# 12_USB3_0_power.net
KiCad netlist of a schematic drawn in Altium Designer
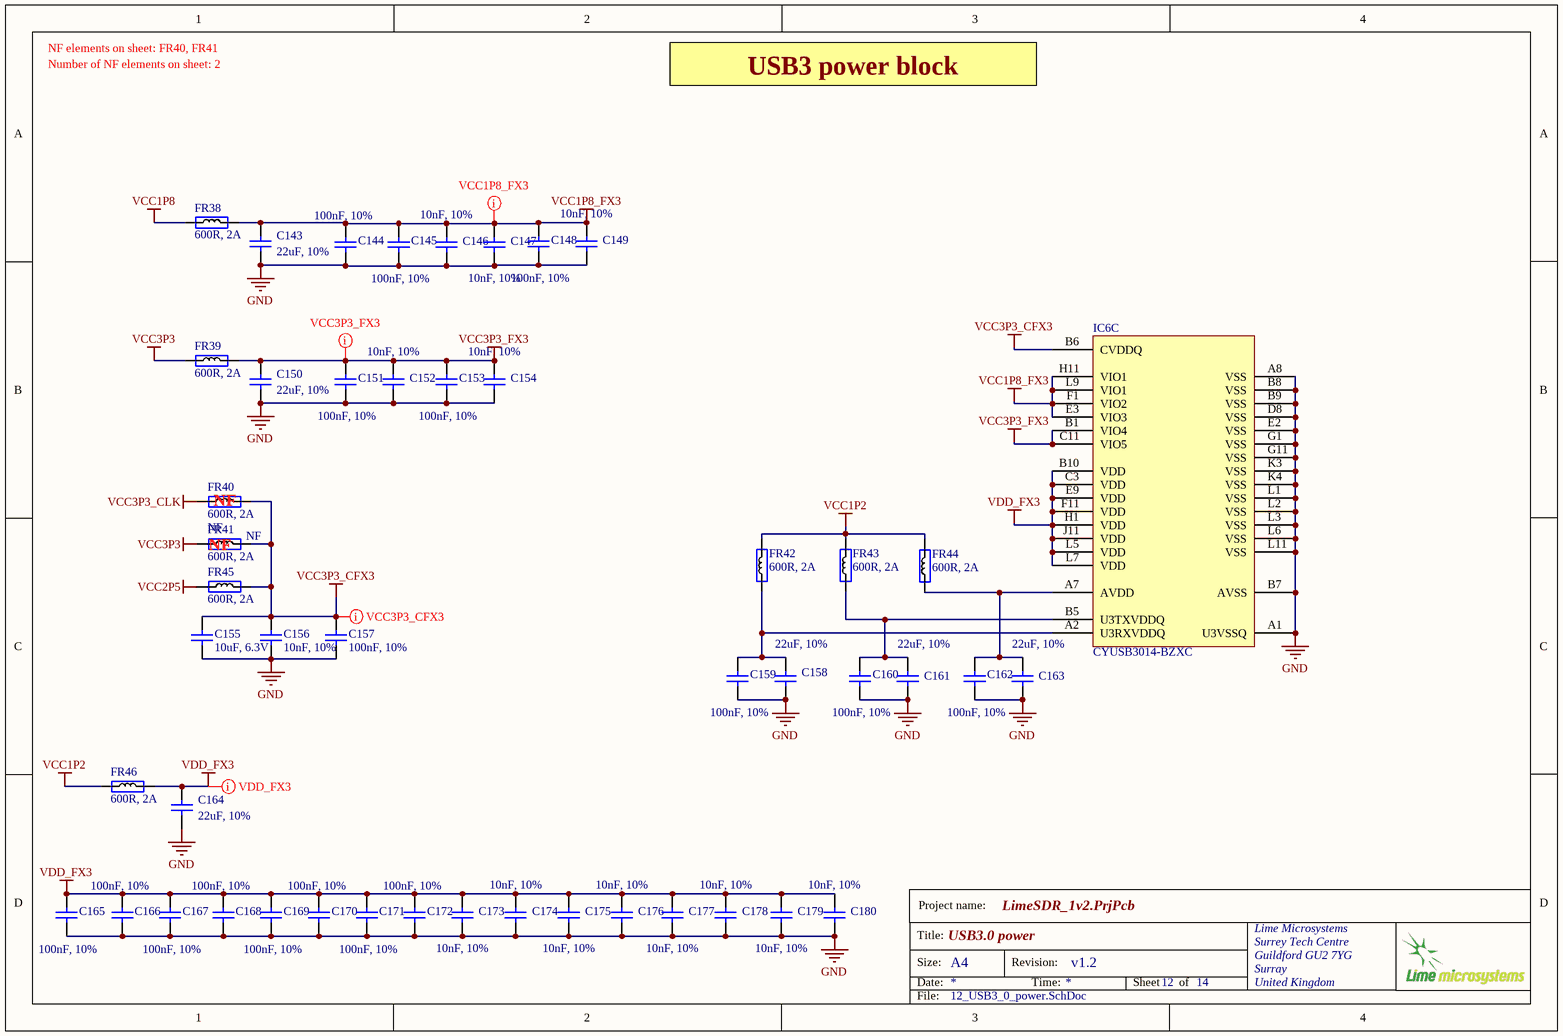
[diagram p0: 12_USB3_0_power.SchDoc]

(export (version "E")
  (design (tool "Eeschema 10.0.6"))
  (components
    (comp (ref "C143")
      (value "22uF, 10%")
      (footprint "CAP0603")
      (fields (field (name "TOLERANCE") "20 %"))
      (libsource (lib "LimeFPGAboard_schLib") (part "Cap_0603"))
    )
    (comp (ref "C144")
      (value "100nF, 10%")
      (footprint "CAP0402")
      (fields
        (field (name "TOLERANCE") "10 %")
        (field (name "MANUFACTURER") "Murata Electronics")
        (field (name "MANUFACTURER PART NUMBER") "GRM155R71C104KA88D")
      )
      (libsource (lib "LimeFPGAboard_schLib") (part "Cap_0603"))
    )
    (comp (ref "C145")
      (value "100nF, 10%")
      (footprint "CAP0402")
      (fields
        (field (name "TOLERANCE") "10 %")
        (field (name "MANUFACTURER") "Murata Electronics")
        (field (name "MANUFACTURER PART NUMBER") "GRM155R71C104KA88D")
      )
      (libsource (lib "LimeFPGAboard_schLib") (part "Cap_0603"))
    )
    (comp (ref "C146")
      (value "10nF, 10%")
      (footprint "CAP0402")
      (fields (field (name "TOLERANCE") "±10%") (field (name "MANUFACTURER") "Yageo"))
      (libsource (lib "LimeFPGAboard_schLib") (part "Cap_0603"))
    )
    (comp (ref "C147")
      (value "10nF, 10%")
      (footprint "CAP0402")
      (fields (field (name "TOLERANCE") "±10%") (field (name "MANUFACTURER") "Yageo"))
      (libsource (lib "LimeFPGAboard_schLib") (part "Cap_0603"))
    )
    (comp (ref "C148")
      (value "100nF, 10%")
      (footprint "CAP0402")
      (fields
        (field (name "TOLERANCE") "10 %")
        (field (name "MANUFACTURER") "Murata Electronics")
        (field (name "MANUFACTURER PART NUMBER") "GRM155R71C104KA88D")
      )
      (libsource (lib "LimeFPGAboard_schLib") (part "Cap_0603"))
    )
    (comp (ref "C149")
      (value "10nF, 10%")
      (footprint "CAP0402")
      (fields (field (name "TOLERANCE") "±10%") (field (name "MANUFACTURER") "Yageo"))
      (libsource (lib "LimeFPGAboard_schLib") (part "Cap_0603"))
    )
    (comp (ref "C150")
      (value "22uF, 10%")
      (footprint "CAP0603")
      (fields (field (name "TOLERANCE") "20 %"))
      (libsource (lib "LimeFPGAboard_schLib") (part "Cap_0603"))
    )
    (comp (ref "C151")
      (value "100nF, 10%")
      (footprint "CAP0402")
      (fields
        (field (name "TOLERANCE") "10 %")
        (field (name "MANUFACTURER") "Murata Electronics")
        (field (name "MANUFACTURER PART NUMBER") "GRM155R71C104KA88D")
      )
      (libsource (lib "LimeFPGAboard_schLib") (part "Cap_0603"))
    )
    (comp (ref "C152")
      (value "10nF, 10%")
      (footprint "CAP0402")
      (fields (field (name "TOLERANCE") "±10%") (field (name "MANUFACTURER") "Yageo"))
      (libsource (lib "LimeFPGAboard_schLib") (part "Cap_0603"))
    )
    (comp (ref "C153")
      (value "100nF, 10%")
      (footprint "CAP0402")
      (fields
        (field (name "TOLERANCE") "10 %")
        (field (name "MANUFACTURER") "Murata Electronics")
        (field (name "MANUFACTURER PART NUMBER") "GRM155R71C104KA88D")
      )
      (libsource (lib "LimeFPGAboard_schLib") (part "Cap_0603"))
    )
    (comp (ref "C154")
      (value "10nF, 10%")
      (footprint "CAP0402")
      (fields (field (name "TOLERANCE") "±10%") (field (name "MANUFACTURER") "Yageo"))
      (libsource (lib "LimeFPGAboard_schLib") (part "Cap_0603"))
    )
    (comp (ref "C155")
      (value "10uF, 6.3V")
      (footprint "CAP0603")
      (fields (field (name "TOLERANCE") "±20%") (field (name "MANUFACTURER") "Yageo"))
      (libsource (lib "LimeFPGAboard_schLib") (part "Cap_0603"))
    )
    (comp (ref "C156")
      (value "10nF, 10%")
      (footprint "CAP0402")
      (fields (field (name "TOLERANCE") "±10%") (field (name "MANUFACTURER") "Yageo"))
      (libsource (lib "LimeFPGAboard_schLib") (part "Cap_0603"))
    )
    (comp (ref "C157")
      (value "100nF, 10%")
      (footprint "CAP0402")
      (fields
        (field (name "TOLERANCE") "10 %")
        (field (name "MANUFACTURER") "Murata Electronics")
        (field (name "MANUFACTURER PART NUMBER") "GRM155R71C104KA88D")
      )
      (libsource (lib "LimeFPGAboard_schLib") (part "Cap_0603"))
    )
    (comp (ref "C158")
      (value "22uF, 10%")
      (footprint "CAP0603")
      (fields (field (name "TOLERANCE") "20 %"))
      (libsource (lib "LimeFPGAboard_schLib") (part "Cap_0603"))
    )
    (comp (ref "C159")
      (value "100nF, 10%")
      (footprint "CAP0402")
      (fields
        (field (name "TOLERANCE") "10 %")
        (field (name "MANUFACTURER") "Murata Electronics")
        (field (name "MANUFACTURER PART NUMBER") "GRM155R71C104KA88D")
      )
      (libsource (lib "LimeFPGAboard_schLib") (part "Cap_0603"))
    )
    (comp (ref "C160")
      (value "100nF, 10%")
      (footprint "CAP0402")
      (fields
        (field (name "TOLERANCE") "10 %")
        (field (name "MANUFACTURER") "Murata Electronics")
        (field (name "MANUFACTURER PART NUMBER") "GRM155R71C104KA88D")
      )
      (libsource (lib "LimeFPGAboard_schLib") (part "Cap_0603"))
    )
    (comp (ref "C161")
      (value "22uF, 10%")
      (footprint "CAP0603")
      (fields (field (name "TOLERANCE") "20 %"))
      (libsource (lib "LimeFPGAboard_schLib") (part "Cap_0603"))
    )
    (comp (ref "C162")
      (value "100nF, 10%")
      (footprint "CAP0402")
      (fields
        (field (name "TOLERANCE") "10 %")
        (field (name "MANUFACTURER") "Murata Electronics")
        (field (name "MANUFACTURER PART NUMBER") "GRM155R71C104KA88D")
      )
      (libsource (lib "LimeFPGAboard_schLib") (part "Cap_0603"))
    )
    (comp (ref "C163")
      (value "22uF, 10%")
      (footprint "CAP0603")
      (fields (field (name "TOLERANCE") "20 %"))
      (libsource (lib "LimeFPGAboard_schLib") (part "Cap_0603"))
    )
    (comp (ref "C164")
      (value "22uF, 10%")
      (footprint "CAP0603")
      (fields (field (name "TOLERANCE") "20 %"))
      (libsource (lib "LimeFPGAboard_schLib") (part "Cap_0603"))
    )
    (comp (ref "C165")
      (value "100nF, 10%")
      (footprint "CAP0402")
      (fields
        (field (name "TOLERANCE") "10 %")
        (field (name "MANUFACTURER") "Murata Electronics")
        (field (name "MANUFACTURER PART NUMBER") "GRM155R71C104KA88D")
      )
      (libsource (lib "LimeFPGAboard_schLib") (part "Cap_0603"))
    )
    (comp (ref "C166")
      (value "100nF, 10%")
      (footprint "CAP0402")
      (fields
        (field (name "TOLERANCE") "10 %")
        (field (name "MANUFACTURER") "Murata Electronics")
        (field (name "MANUFACTURER PART NUMBER") "GRM155R71C104KA88D")
      )
      (libsource (lib "LimeFPGAboard_schLib") (part "Cap_0603"))
    )
    (comp (ref "C167")
      (value "100nF, 10%")
      (footprint "CAP0402")
      (fields
        (field (name "TOLERANCE") "10 %")
        (field (name "MANUFACTURER") "Murata Electronics")
        (field (name "MANUFACTURER PART NUMBER") "GRM155R71C104KA88D")
      )
      (libsource (lib "LimeFPGAboard_schLib") (part "Cap_0603"))
    )
    (comp (ref "C168")
      (value "100nF, 10%")
      (footprint "CAP0402")
      (fields
        (field (name "TOLERANCE") "10 %")
        (field (name "MANUFACTURER") "Murata Electronics")
        (field (name "MANUFACTURER PART NUMBER") "GRM155R71C104KA88D")
      )
      (libsource (lib "LimeFPGAboard_schLib") (part "Cap_0603"))
    )
    (comp (ref "C169")
      (value "100nF, 10%")
      (footprint "CAP0402")
      (fields
        (field (name "TOLERANCE") "10 %")
        (field (name "MANUFACTURER") "Murata Electronics")
        (field (name "MANUFACTURER PART NUMBER") "GRM155R71C104KA88D")
      )
      (libsource (lib "LimeFPGAboard_schLib") (part "Cap_0603"))
    )
    (comp (ref "C170")
      (value "100nF, 10%")
      (footprint "CAP0402")
      (fields
        (field (name "TOLERANCE") "10 %")
        (field (name "MANUFACTURER") "Murata Electronics")
        (field (name "MANUFACTURER PART NUMBER") "GRM155R71C104KA88D")
      )
      (libsource (lib "LimeFPGAboard_schLib") (part "Cap_0603"))
    )
    (comp (ref "C171")
      (value "100nF, 10%")
      (footprint "CAP0402")
      (fields
        (field (name "TOLERANCE") "10 %")
        (field (name "MANUFACTURER") "Murata Electronics")
        (field (name "MANUFACTURER PART NUMBER") "GRM155R71C104KA88D")
      )
      (libsource (lib "LimeFPGAboard_schLib") (part "Cap_0603"))
    )
    (comp (ref "C172")
      (value "100nF, 10%")
      (footprint "CAP0402")
      (fields
        (field (name "TOLERANCE") "10 %")
        (field (name "MANUFACTURER") "Murata Electronics")
        (field (name "MANUFACTURER PART NUMBER") "GRM155R71C104KA88D")
      )
      (libsource (lib "LimeFPGAboard_schLib") (part "Cap_0603"))
    )
    (comp (ref "C173")
      (value "10nF, 10%")
      (footprint "CAP0402")
      (fields (field (name "TOLERANCE") "±10%") (field (name "MANUFACTURER") "Yageo"))
      (libsource (lib "LimeFPGAboard_schLib") (part "Cap_0603"))
    )
    (comp (ref "C174")
      (value "10nF, 10%")
      (footprint "CAP0402")
      (fields (field (name "TOLERANCE") "±10%") (field (name "MANUFACTURER") "Yageo"))
      (libsource (lib "LimeFPGAboard_schLib") (part "Cap_0603"))
    )
    (comp (ref "C175")
      (value "10nF, 10%")
      (footprint "CAP0402")
      (fields (field (name "TOLERANCE") "±10%") (field (name "MANUFACTURER") "Yageo"))
      (libsource (lib "LimeFPGAboard_schLib") (part "Cap_0603"))
    )
    (comp (ref "C176")
      (value "10nF, 10%")
      (footprint "CAP0402")
      (fields (field (name "TOLERANCE") "±10%") (field (name "MANUFACTURER") "Yageo"))
      (libsource (lib "LimeFPGAboard_schLib") (part "Cap_0603"))
    )
    (comp (ref "C177")
      (value "10nF, 10%")
      (footprint "CAP0402")
      (fields (field (name "TOLERANCE") "±10%") (field (name "MANUFACTURER") "Yageo"))
      (libsource (lib "LimeFPGAboard_schLib") (part "Cap_0603"))
    )
    (comp (ref "C178")
      (value "10nF, 10%")
      (footprint "CAP0402")
      (fields (field (name "TOLERANCE") "±10%") (field (name "MANUFACTURER") "Yageo"))
      (libsource (lib "LimeFPGAboard_schLib") (part "Cap_0603"))
    )
    (comp (ref "C179")
      (value "10nF, 10%")
      (footprint "CAP0402")
      (fields (field (name "TOLERANCE") "±10%") (field (name "MANUFACTURER") "Yageo"))
      (libsource (lib "LimeFPGAboard_schLib") (part "Cap_0603"))
    )
    (comp (ref "C180")
      (value "10nF, 10%")
      (footprint "CAP0402")
      (fields (field (name "TOLERANCE") "±10%") (field (name "MANUFACTURER") "Yageo"))
      (libsource (lib "LimeFPGAboard_schLib") (part "Cap_0603"))
    )
    (comp (ref "FR38")
      (value "600R, 2A")
      (footprint "RES0805")
      (fields (field (name "MANUFACTURER") "TDK"))
      (libsource (lib "LimeFPGAboard_schLib") (part "Ferrite"))
    )
    (comp (ref "FR39")
      (value "600R, 2A")
      (footprint "RES0805")
      (fields (field (name "MANUFACTURER") "TDK"))
      (libsource (lib "LimeFPGAboard_schLib") (part "Ferrite"))
    )
    (comp (ref "FR40")
      (value "600R, 2A")
      (footprint "RES0805")
      (fields (field (name "MANUFACTURER") "TDK") (field (name "ASSEMBLY INFO") "NF"))
      (libsource (lib "") (part "Ferrite_1"))
    )
    (comp (ref "FR41")
      (value "600R, 2A")
      (footprint "RES0805")
      (fields (field (name "MANUFACTURER") "TDK") (field (name "ASSEMBLY INFO") "NF"))
      (libsource (lib "") (part "Ferrite_1"))
    )
    (comp (ref "FR42")
      (value "600R, 2A")
      (footprint "RES0805")
      (fields (field (name "MANUFACTURER") "TDK"))
      (libsource (lib "LimeFPGAboard_schLib") (part "Ferrite"))
    )
    (comp (ref "FR43")
      (value "600R, 2A")
      (footprint "RES0805")
      (fields (field (name "MANUFACTURER") "TDK"))
      (libsource (lib "LimeFPGAboard_schLib") (part "Ferrite"))
    )
    (comp (ref "FR44")
      (value "600R, 2A")
      (footprint "RES0805")
      (fields (field (name "MANUFACTURER") "TDK"))
      (libsource (lib "LimeFPGAboard_schLib") (part "Ferrite"))
    )
    (comp (ref "FR45")
      (value "600R, 2A")
      (footprint "RES0805")
      (fields (field (name "MANUFACTURER") "TDK"))
      (libsource (lib "") (part "Ferrite_1"))
    )
    (comp (ref "FR46")
      (value "600R, 2A")
      (footprint "RES0805")
      (fields (field (name "MANUFACTURER") "TDK"))
      (libsource (lib "LimeFPGAboard_schLib") (part "Ferrite"))
    )
    (comp (ref "IC6")
      (value "CYUSB3014-BZXC")
      (footprint "CYP-BZX121")
      (description "EZ-USB(R) FX3: SuperSpeed USB Controller, 512 KB, 60 I/Os, 0 to 70 degC, 121-Pin FBGA (BZX121)")
      (fields (field (name "MANUFACTURER") "Cypress Semiconductor Corp"))
      (libsource (lib "LimeMicroAltiumLib_schLib") (part "CYUSB3014-BZXC"))
    )
  )
  (nets
    (net (code "1") (name "GND") (class "Default")
      (node (ref "C143") (pin "1") (pinfunction "1_1") (pintype "passive"))
      (node (ref "C144") (pin "2") (pinfunction "2_2") (pintype "passive"))
      (node (ref "C145") (pin "2") (pinfunction "2_2") (pintype "passive"))
      (node (ref "C146") (pin "1") (pinfunction "1_1") (pintype "passive"))
      (node (ref "C147") (pin "1") (pinfunction "1_1") (pintype "passive"))
      (node (ref "C148") (pin "2") (pinfunction "2_2") (pintype "passive"))
      (node (ref "C149") (pin "1") (pinfunction "1_1") (pintype "passive"))
      (node (ref "C150") (pin "1") (pinfunction "1_1") (pintype "passive"))
      (node (ref "C151") (pin "2") (pinfunction "2_2") (pintype "passive"))
      (node (ref "C152") (pin "1") (pinfunction "1_1") (pintype "passive"))
      (node (ref "C153") (pin "2") (pinfunction "2_2") (pintype "passive"))
      (node (ref "C154") (pin "1") (pinfunction "1_1") (pintype "passive"))
      (node (ref "C155") (pin "1") (pinfunction "1_1") (pintype "passive"))
      (node (ref "C156") (pin "1") (pinfunction "1_1") (pintype "passive"))
      (node (ref "C157") (pin "2") (pinfunction "2_2") (pintype "passive"))
      (node (ref "C158") (pin "1") (pinfunction "1_1") (pintype "passive"))
      (node (ref "C159") (pin "2") (pinfunction "2_2") (pintype "passive"))
      (node (ref "C160") (pin "2") (pinfunction "2_2") (pintype "passive"))
      (node (ref "C161") (pin "1") (pinfunction "1_1") (pintype "passive"))
      (node (ref "C162") (pin "2") (pinfunction "2_2") (pintype "passive"))
      (node (ref "C163") (pin "1") (pinfunction "1_1") (pintype "passive"))
      (node (ref "C164") (pin "1") (pinfunction "1_1") (pintype "passive"))
      (node (ref "C165") (pin "2") (pinfunction "2_2") (pintype "passive"))
      (node (ref "C166") (pin "2") (pinfunction "2_2") (pintype "passive"))
      (node (ref "C167") (pin "2") (pinfunction "2_2") (pintype "passive"))
      (node (ref "C168") (pin "2") (pinfunction "2_2") (pintype "passive"))
      (node (ref "C169") (pin "2") (pinfunction "2_2") (pintype "passive"))
      (node (ref "C170") (pin "2") (pinfunction "2_2") (pintype "passive"))
      (node (ref "C171") (pin "2") (pinfunction "2_2") (pintype "passive"))
      (node (ref "C172") (pin "2") (pinfunction "2_2") (pintype "passive"))
      (node (ref "C173") (pin "1") (pinfunction "1_1") (pintype "passive"))
      (node (ref "C174") (pin "1") (pinfunction "1_1") (pintype "passive"))
      (node (ref "C175") (pin "1") (pinfunction "1_1") (pintype "passive"))
      (node (ref "C176") (pin "1") (pinfunction "1_1") (pintype "passive"))
      (node (ref "C177") (pin "1") (pinfunction "1_1") (pintype "passive"))
      (node (ref "C178") (pin "1") (pinfunction "1_1") (pintype "passive"))
      (node (ref "C179") (pin "1") (pinfunction "1_1") (pintype "passive"))
      (node (ref "C180") (pin "1") (pinfunction "1_1") (pintype "passive"))
      (node (ref "IC6") (pin "A1") (pinfunction "U3VSSQ_A1") (pintype "power_in"))
      (node (ref "IC6") (pin "A8") (pinfunction "VSS_A8") (pintype "power_in"))
      (node (ref "IC6") (pin "B7") (pinfunction "AVSS_B7") (pintype "power_in"))
      (node (ref "IC6") (pin "B8") (pinfunction "VSS_B8") (pintype "power_in"))
      (node (ref "IC6") (pin "B9") (pinfunction "VSS_B9") (pintype "power_in"))
      (node (ref "IC6") (pin "D8") (pinfunction "VSS_D8") (pintype "power_in"))
      (node (ref "IC6") (pin "E2") (pinfunction "VSS_E2") (pintype "power_in"))
      (node (ref "IC6") (pin "G1") (pinfunction "VSS_G1") (pintype "power_in"))
      (node (ref "IC6") (pin "G11") (pinfunction "VSS_G11") (pintype "power_in"))
      (node (ref "IC6") (pin "K3") (pinfunction "VSS_K3") (pintype "power_in"))
      (node (ref "IC6") (pin "K4") (pinfunction "VSS_K4") (pintype "power_in"))
      (node (ref "IC6") (pin "L1") (pinfunction "VSS_L1") (pintype "power_in"))
      (node (ref "IC6") (pin "L11") (pinfunction "VSS_L11") (pintype "power_in"))
      (node (ref "IC6") (pin "L2") (pinfunction "VSS_L2") (pintype "power_in"))
      (node (ref "IC6") (pin "L3") (pinfunction "VSS_L3") (pintype "power_in"))
      (node (ref "IC6") (pin "L6") (pinfunction "VSS_L6") (pintype "power_in"))
    )
    (net (code "2") (name "Net-(IC6C-AVDD)") (class "Default")
      (node (ref "C162") (pin "1") (pinfunction "1_1") (pintype "passive"))
      (node (ref "C163") (pin "2") (pinfunction "2_2") (pintype "passive"))
      (node (ref "FR44") (pin "1") (pinfunction "1_1") (pintype "passive"))
      (node (ref "IC6") (pin "A7") (pinfunction "AVDD_A7") (pintype "power_in"))
    )
    (net (code "3") (name "Net-(IC6C-U3RXVDDQ)") (class "Default")
      (node (ref "C158") (pin "2") (pinfunction "2_2") (pintype "passive"))
      (node (ref "C159") (pin "1") (pinfunction "1_1") (pintype "passive"))
      (node (ref "FR42") (pin "1") (pinfunction "1_1") (pintype "passive"))
      (node (ref "IC6") (pin "A2") (pinfunction "U3RXVDDQ_A2") (pintype "power_in"))
    )
    (net (code "4") (name "Net-(IC6C-U3TXVDDQ)") (class "Default")
      (node (ref "C160") (pin "1") (pinfunction "1_1") (pintype "passive"))
      (node (ref "C161") (pin "2") (pinfunction "2_2") (pintype "passive"))
      (node (ref "FR43") (pin "1") (pinfunction "1_1") (pintype "passive"))
      (node (ref "IC6") (pin "B5") (pinfunction "U3TXVDDQ_B5") (pintype "power_in"))
    )
    (net (code "5") (name "VCC1P2") (class "Default")
      (node (ref "FR42") (pin "2") (pinfunction "2_2") (pintype "passive"))
      (node (ref "FR43") (pin "2") (pinfunction "2_2") (pintype "passive"))
      (node (ref "FR44") (pin "2") (pinfunction "2_2") (pintype "passive"))
      (node (ref "FR46") (pin "1") (pinfunction "1_1") (pintype "passive"))
    )
    (net (code "6") (name "VCC1P8") (class "Default")
      (node (ref "FR38") (pin "1") (pinfunction "1_1") (pintype "passive"))
    )
    (net (code "7") (name "VCC1P8_FX3") (class "Default")
      (node (ref "C143") (pin "2") (pinfunction "2_2") (pintype "passive"))
      (node (ref "C144") (pin "1") (pinfunction "1_1") (pintype "passive"))
      (node (ref "C145") (pin "1") (pinfunction "1_1") (pintype "passive"))
      (node (ref "C146") (pin "2") (pinfunction "2_2") (pintype "passive"))
      (node (ref "C147") (pin "2") (pinfunction "2_2") (pintype "passive"))
      (node (ref "C148") (pin "1") (pinfunction "1_1") (pintype "passive"))
      (node (ref "C149") (pin "2") (pinfunction "2_2") (pintype "passive"))
      (node (ref "FR38") (pin "2") (pinfunction "2_2") (pintype "passive"))
      (node (ref "IC6") (pin "E3") (pinfunction "VIO3_E3") (pintype "power_in"))
      (node (ref "IC6") (pin "F1") (pinfunction "VIO2_F1") (pintype "power_in"))
      (node (ref "IC6") (pin "H11") (pinfunction "VIO1_H11") (pintype "power_in"))
      (node (ref "IC6") (pin "L9") (pinfunction "VIO1_L9") (pintype "power_in"))
    )
    (net (code "8") (name "VCC2P5") (class "Default")
      (node (ref "FR45") (pin "2") (pinfunction "2_2") (pintype "passive"))
    )
    (net (code "9") (name "VCC3P3") (class "Default")
      (node (ref "FR39") (pin "1") (pinfunction "1_1") (pintype "passive"))
      (node (ref "FR41") (pin "2") (pinfunction "2_2") (pintype "passive"))
    )
    (net (code "10") (name "VCC3P3_CFX3") (class "Default")
      (node (ref "C155") (pin "2") (pinfunction "2_2") (pintype "passive"))
      (node (ref "C156") (pin "2") (pinfunction "2_2") (pintype "passive"))
      (node (ref "C157") (pin "1") (pinfunction "1_1") (pintype "passive"))
      (node (ref "FR40") (pin "1") (pinfunction "1_1") (pintype "passive"))
      (node (ref "FR41") (pin "1") (pinfunction "1_1") (pintype "passive"))
      (node (ref "FR45") (pin "1") (pinfunction "1_1") (pintype "passive"))
      (node (ref "IC6") (pin "B6") (pinfunction "CVDDQ_B6") (pintype "power_in"))
    )
    (net (code "11") (name "VCC3P3_CLK") (class "Default")
      (node (ref "FR40") (pin "2") (pinfunction "2_2") (pintype "passive"))
    )
    (net (code "12") (name "VCC3P3_FX3") (class "Default")
      (node (ref "C150") (pin "2") (pinfunction "2_2") (pintype "passive"))
      (node (ref "C151") (pin "1") (pinfunction "1_1") (pintype "passive"))
      (node (ref "C152") (pin "2") (pinfunction "2_2") (pintype "passive"))
      (node (ref "C153") (pin "1") (pinfunction "1_1") (pintype "passive"))
      (node (ref "C154") (pin "2") (pinfunction "2_2") (pintype "passive"))
      (node (ref "FR39") (pin "2") (pinfunction "2_2") (pintype "passive"))
      (node (ref "IC6") (pin "B1") (pinfunction "VIO4_B1") (pintype "power_in"))
      (node (ref "IC6") (pin "C11") (pinfunction "VIO5_C11") (pintype "power_in"))
    )
    (net (code "13") (name "VDD_FX3") (class "Default")
      (node (ref "C164") (pin "2") (pinfunction "2_2") (pintype "passive"))
      (node (ref "C165") (pin "1") (pinfunction "1_1") (pintype "passive"))
      (node (ref "C166") (pin "1") (pinfunction "1_1") (pintype "passive"))
      (node (ref "C167") (pin "1") (pinfunction "1_1") (pintype "passive"))
      (node (ref "C168") (pin "1") (pinfunction "1_1") (pintype "passive"))
      (node (ref "C169") (pin "1") (pinfunction "1_1") (pintype "passive"))
      (node (ref "C170") (pin "1") (pinfunction "1_1") (pintype "passive"))
      (node (ref "C171") (pin "1") (pinfunction "1_1") (pintype "passive"))
      (node (ref "C172") (pin "1") (pinfunction "1_1") (pintype "passive"))
      (node (ref "C173") (pin "2") (pinfunction "2_2") (pintype "passive"))
      (node (ref "C174") (pin "2") (pinfunction "2_2") (pintype "passive"))
      (node (ref "C175") (pin "2") (pinfunction "2_2") (pintype "passive"))
      (node (ref "C176") (pin "2") (pinfunction "2_2") (pintype "passive"))
      (node (ref "C177") (pin "2") (pinfunction "2_2") (pintype "passive"))
      (node (ref "C178") (pin "2") (pinfunction "2_2") (pintype "passive"))
      (node (ref "C179") (pin "2") (pinfunction "2_2") (pintype "passive"))
      (node (ref "C180") (pin "2") (pinfunction "2_2") (pintype "passive"))
      (node (ref "FR46") (pin "2") (pinfunction "2_2") (pintype "passive"))
      (node (ref "IC6") (pin "B10") (pinfunction "VDD_B10") (pintype "power_in"))
      (node (ref "IC6") (pin "C3") (pinfunction "VDD_C3") (pintype "power_in"))
      (node (ref "IC6") (pin "E9") (pinfunction "VDD_E9") (pintype "power_in"))
      (node (ref "IC6") (pin "F11") (pinfunction "VDD_F11") (pintype "power_in"))
      (node (ref "IC6") (pin "H1") (pinfunction "VDD_H1") (pintype "power_in"))
      (node (ref "IC6") (pin "J11") (pinfunction "VDD_J11") (pintype "power_in"))
      (node (ref "IC6") (pin "L5") (pinfunction "VDD_L5") (pintype "power_in"))
      (node (ref "IC6") (pin "L7") (pinfunction "VDD_L7") (pintype "power_in"))
    )
  )
)
